# SMART_SOCKET.net
KiCad netlist of a schematic drawn in EAGLE
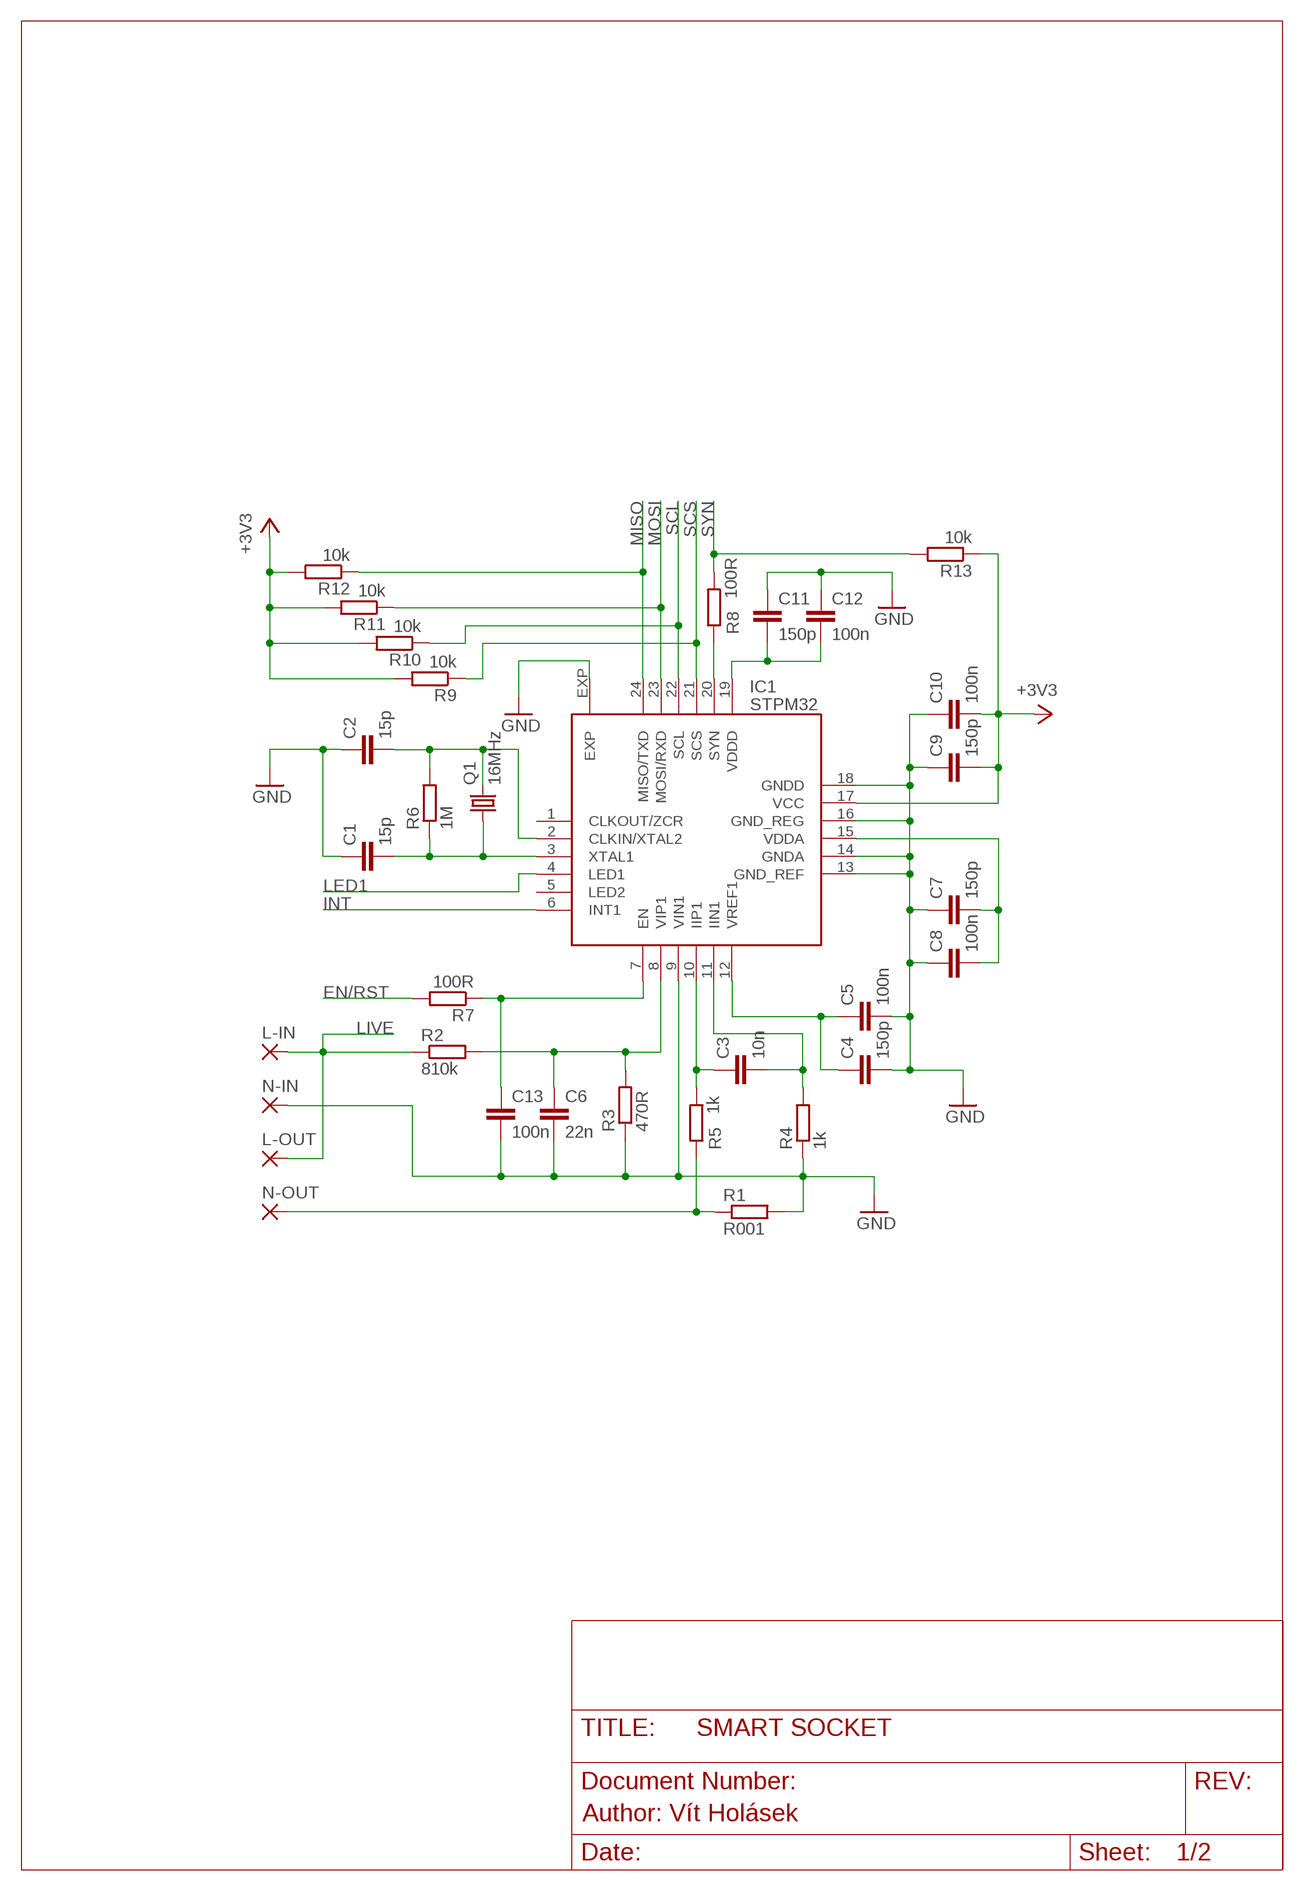
[diagram p0: schematic, sheet 1]
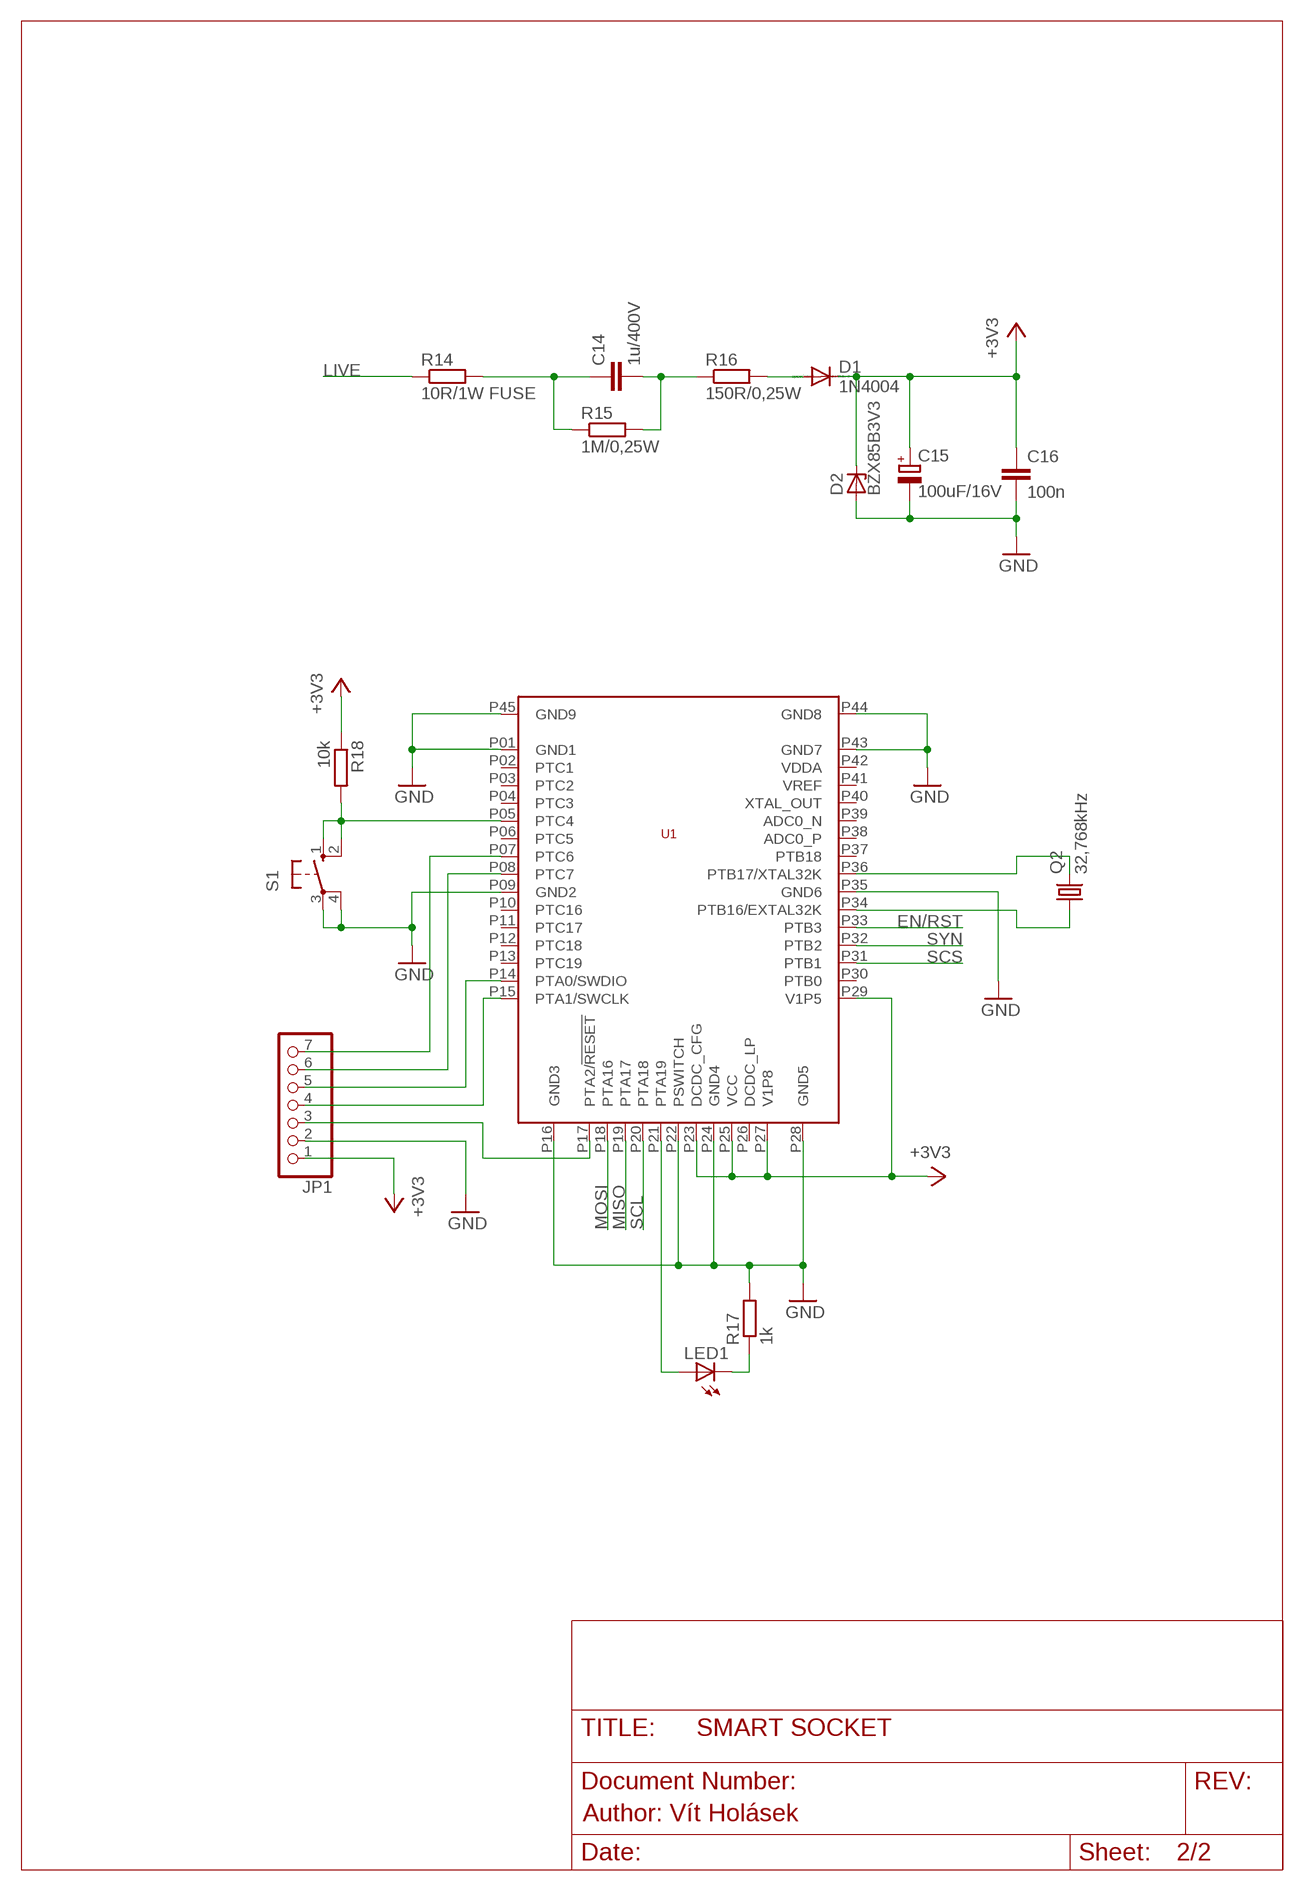
[diagram p1: schematic, sheet 2]

(export (version "E")
  (design (tool "Eeschema 10.0.6"))
  (components
    (comp (ref "C1")
      (value "15p")
      (footprint "eagle-import:C0402")
      (libsource (lib "eagle-import") (part "C-EUC0402"))
    )
    (comp (ref "C2")
      (value "15p")
      (footprint "eagle-import:C0402")
      (libsource (lib "eagle-import") (part "C-EUC0402"))
    )
    (comp (ref "C3")
      (value "10n")
      (footprint "eagle-import:C0402")
      (libsource (lib "eagle-import") (part "C-EUC0402"))
    )
    (comp (ref "C4")
      (value "150p")
      (footprint "eagle-import:C0402")
      (libsource (lib "eagle-import") (part "C-EUC0402"))
    )
    (comp (ref "C5")
      (value "100n")
      (footprint "eagle-import:C0402")
      (libsource (lib "eagle-import") (part "C-EUC0402"))
    )
    (comp (ref "C6")
      (value "22n")
      (footprint "eagle-import:C0603")
      (libsource (lib "eagle-import") (part "C-EUC0603"))
    )
    (comp (ref "C7")
      (value "150p")
      (footprint "eagle-import:C0402")
      (libsource (lib "eagle-import") (part "C-EUC0402"))
    )
    (comp (ref "C8")
      (value "100n")
      (footprint "eagle-import:C0402")
      (libsource (lib "eagle-import") (part "C-EUC0402"))
    )
    (comp (ref "C9")
      (value "150p")
      (footprint "eagle-import:C0402")
      (libsource (lib "eagle-import") (part "C-EUC0402"))
    )
    (comp (ref "C10")
      (value "100n")
      (footprint "eagle-import:C0402")
      (libsource (lib "eagle-import") (part "C-EUC0402"))
    )
    (comp (ref "C11")
      (value "150p")
      (footprint "eagle-import:C0402")
      (libsource (lib "eagle-import") (part "C-EUC0402"))
    )
    (comp (ref "C12")
      (value "100n")
      (footprint "eagle-import:C0402")
      (libsource (lib "eagle-import") (part "C-EUC0402"))
    )
    (comp (ref "C13")
      (value "100n")
      (footprint "eagle-import:C0603")
      (libsource (lib "eagle-import") (part "C-EUC0603"))
    )
    (comp (ref "IC1")
      (value "STPM32")
      (footprint "eagle-import:QFN24L")
      (libsource (lib "eagle-import") (part "STPM32"))
    )
    (comp (ref "L-IN")
      (value "2,54/1,1")
      (footprint "eagle-import:2,54_1,1")
      (libsource (lib "eagle-import") (part "2,54/1,1"))
    )
    (comp (ref "L-OUT")
      (value "2,54/1,1")
      (footprint "eagle-import:2,54_1,1")
      (libsource (lib "eagle-import") (part "2,54/1,1"))
    )
    (comp (ref "N-IN")
      (value "2,54/1,1")
      (footprint "eagle-import:2,54_1,1")
      (libsource (lib "eagle-import") (part "2,54/1,1"))
    )
    (comp (ref "N-OUT")
      (value "2,54/1,1")
      (footprint "eagle-import:2,54_1,1")
      (libsource (lib "eagle-import") (part "2,54/1,1"))
    )
    (comp (ref "Q1")
      (value "16MHz")
      (footprint "eagle-import:CTS406")
      (libsource (lib "eagle-import") (part "CRYSTALCTS406"))
    )
    (comp (ref "R1")
      (value "R001")
      (footprint "eagle-import:R2512")
      (libsource (lib "eagle-import") (part "R-EU_R2512"))
    )
    (comp (ref "R2")
      (value "810k")
      (footprint "eagle-import:R0603")
      (libsource (lib "eagle-import") (part "R-EU_R0603"))
    )
    (comp (ref "R3")
      (value "470R")
      (footprint "eagle-import:R0603")
      (libsource (lib "eagle-import") (part "R-EU_R0603"))
    )
    (comp (ref "R4")
      (value "1k")
      (footprint "eagle-import:R0402")
      (libsource (lib "eagle-import") (part "R-EU_R0402"))
    )
    (comp (ref "R5")
      (value "1k")
      (footprint "eagle-import:R0402")
      (libsource (lib "eagle-import") (part "R-EU_R0402"))
    )
    (comp (ref "R6")
      (value "1M")
      (footprint "eagle-import:R0402")
      (libsource (lib "eagle-import") (part "R-EU_R0402"))
    )
    (comp (ref "R7")
      (value "100R")
      (footprint "eagle-import:R0402")
      (libsource (lib "eagle-import") (part "R-EU_R0402"))
    )
    (comp (ref "R8")
      (value "100R")
      (footprint "eagle-import:R0402")
      (libsource (lib "eagle-import") (part "R-EU_R0402"))
    )
    (comp (ref "R9")
      (value "10k")
      (footprint "eagle-import:R0402")
      (libsource (lib "eagle-import") (part "R-EU_R0402"))
    )
    (comp (ref "R10")
      (value "10k")
      (footprint "eagle-import:R0402")
      (libsource (lib "eagle-import") (part "R-EU_R0402"))
    )
    (comp (ref "R11")
      (value "10k")
      (footprint "eagle-import:R0402")
      (libsource (lib "eagle-import") (part "R-EU_R0402"))
    )
    (comp (ref "R12")
      (value "10k")
      (footprint "eagle-import:R0402")
      (libsource (lib "eagle-import") (part "R-EU_R0402"))
    )
    (comp (ref "R13")
      (value "10k")
      (footprint "eagle-import:R0402")
      (libsource (lib "eagle-import") (part "R-EU_R0402"))
    )
    (comp (ref "C14")
      (value "1u/400V")
      (footprint "eagle-import:C0805")
      (libsource (lib "eagle-import") (part "C-EUC0805"))
    )
    (comp (ref "C15")
      (value "100uF/16V")
      (footprint "eagle-import:E5-8,5")
      (libsource (lib "eagle-import") (part "CPOL-EUE5-8.5"))
    )
    (comp (ref "C16")
      (value "100n")
      (footprint "eagle-import:C0603")
      (libsource (lib "eagle-import") (part "C-EUC0603"))
    )
    (comp (ref "D1")
      (value "1N4004")
      (footprint "eagle-import:DO41-10")
      (libsource (lib "eagle-import") (part "1N4004"))
    )
    (comp (ref "D2")
      (value "BZX85B3V3")
      (footprint "eagle-import:DO41Z10")
      (libsource (lib "eagle-import") (part "ZENER-DIODEDO41Z10"))
    )
    (comp (ref "JP1")
      (value "PINHD-1X7")
      (footprint "eagle-import:1X07")
      (libsource (lib "eagle-import") (part "PINHD-1X7"))
    )
    (comp (ref "LED1")
      (value "LED3MM")
      (footprint "eagle-import:LED3MM")
      (libsource (lib "eagle-import") (part "LED3MM"))
    )
    (comp (ref "Q2")
      (value "32,768kHz")
      (footprint "eagle-import:TC26V")
      (libsource (lib "eagle-import") (part "CRYSTALTC26V"))
    )
    (comp (ref "R14")
      (value "10R/1W FUSE")
      (footprint "eagle-import:0204_7")
      (libsource (lib "eagle-import") (part "R-EU_0204/7"))
    )
    (comp (ref "R15")
      (value "1M/0,25W")
      (footprint "eagle-import:R0805")
      (libsource (lib "eagle-import") (part "R-EU_R0805"))
    )
    (comp (ref "R16")
      (value "150R/0,25W")
      (footprint "eagle-import:R0805")
      (libsource (lib "eagle-import") (part "R-EU_R0805"))
    )
    (comp (ref "R17")
      (value "1k")
      (footprint "eagle-import:R0402")
      (libsource (lib "eagle-import") (part "R-EU_R0402"))
    )
    (comp (ref "R18")
      (value "10k")
      (footprint "eagle-import:R0402")
      (libsource (lib "eagle-import") (part "R-EU_R0402"))
    )
    (comp (ref "S1")
      (value "10-XX")
      (footprint "eagle-import:B3F-10XX")
      (fields (field (name "MPN") "B3F-1000"))
      (libsource (lib "eagle-import") (part "10-XX"))
    )
    (comp (ref "U1")
      (value "R41Z-T")
      (footprint "eagle-import:R41Z")
      (libsource (lib "eagle-import") (part "R41Z-T"))
    )
  )
  (nets
    (net (code "1") (name "+3V3") (class "Default")
      (node (ref "C10") (pin "2") (pinfunction "2_2") (pintype "passive"))
      (node (ref "C15") (pin "+") (pinfunction "+_+") (pintype "passive"))
      (node (ref "C16") (pin "1") (pinfunction "1_1") (pintype "passive"))
      (node (ref "C9") (pin "2") (pinfunction "2_2") (pintype "passive"))
      (node (ref "D1") (pin "C") (pinfunction "C_C") (pintype "passive"))
      (node (ref "D2") (pin "C") (pinfunction "C_C") (pintype "passive"))
      (node (ref "IC1") (pin "17") (pinfunction "VCC_17") (pintype "bidirectional"))
      (node (ref "JP1") (pin "1") (pinfunction "1_1") (pintype "passive"))
      (node (ref "R10") (pin "2") (pinfunction "2_2") (pintype "passive"))
      (node (ref "R11") (pin "2") (pinfunction "2_2") (pintype "passive"))
      (node (ref "R12") (pin "2") (pinfunction "2_2") (pintype "passive"))
      (node (ref "R13") (pin "1") (pinfunction "1_1") (pintype "passive"))
      (node (ref "R18") (pin "1") (pinfunction "1_1") (pintype "passive"))
      (node (ref "R9") (pin "2") (pinfunction "2_2") (pintype "passive"))
      (node (ref "U1") (pin "P23") (pinfunction "DCDC_CFG_P23") (pintype "bidirectional"))
      (node (ref "U1") (pin "P25") (pinfunction "VCC_P25") (pintype "bidirectional"))
      (node (ref "U1") (pin "P27") (pinfunction "V1P8_P27") (pintype "bidirectional"))
      (node (ref "U1") (pin "P29") (pinfunction "V1P5_P29") (pintype "bidirectional"))
    )
    (net (code "2") (name "EN{slash}RST") (class "Default")
      (node (ref "R7") (pin "2") (pinfunction "2_2") (pintype "passive"))
      (node (ref "U1") (pin "P33") (pinfunction "PTB3_P33") (pintype "bidirectional"))
    )
    (net (code "3") (name "GND") (class "Default")
      (node (ref "C1") (pin "1") (pinfunction "1_1") (pintype "passive"))
      (node (ref "C10") (pin "1") (pinfunction "1_1") (pintype "passive"))
      (node (ref "C11") (pin "1") (pinfunction "1_1") (pintype "passive"))
      (node (ref "C12") (pin "1") (pinfunction "1_1") (pintype "passive"))
      (node (ref "C13") (pin "2") (pinfunction "2_2") (pintype "passive"))
      (node (ref "C15") (pin "-") (pinfunction "-_-") (pintype "passive"))
      (node (ref "C16") (pin "2") (pinfunction "2_2") (pintype "passive"))
      (node (ref "C2") (pin "1") (pinfunction "1_1") (pintype "passive"))
      (node (ref "C4") (pin "2") (pinfunction "2_2") (pintype "passive"))
      (node (ref "C5") (pin "2") (pinfunction "2_2") (pintype "passive"))
      (node (ref "C6") (pin "2") (pinfunction "2_2") (pintype "passive"))
      (node (ref "C7") (pin "1") (pinfunction "1_1") (pintype "passive"))
      (node (ref "C8") (pin "1") (pinfunction "1_1") (pintype "passive"))
      (node (ref "C9") (pin "1") (pinfunction "1_1") (pintype "passive"))
      (node (ref "D2") (pin "A") (pinfunction "A_A") (pintype "passive"))
      (node (ref "IC1") (pin "13") (pinfunction "GND_REF_13") (pintype "bidirectional"))
      (node (ref "IC1") (pin "14") (pinfunction "GNDA_14") (pintype "bidirectional"))
      (node (ref "IC1") (pin "16") (pinfunction "GND_REG_16") (pintype "bidirectional"))
      (node (ref "IC1") (pin "18") (pinfunction "GNDD_18") (pintype "bidirectional"))
      (node (ref "IC1") (pin "9") (pinfunction "VIN1_9") (pintype "bidirectional"))
      (node (ref "IC1") (pin "EXP") (pinfunction "EXP_EXP") (pintype "bidirectional"))
      (node (ref "JP1") (pin "2") (pinfunction "2_2") (pintype "passive"))
      (node (ref "N-IN") (pin "1") (pinfunction "P_1") (pintype "passive"))
      (node (ref "R1") (pin "2") (pinfunction "2_2") (pintype "passive"))
      (node (ref "R17") (pin "2") (pinfunction "2_2") (pintype "passive"))
      (node (ref "R3") (pin "1") (pinfunction "1_1") (pintype "passive"))
      (node (ref "R4") (pin "1") (pinfunction "1_1") (pintype "passive"))
      (node (ref "S1") (pin "3") (pinfunction "P_3") (pintype "passive"))
      (node (ref "S1") (pin "4") (pinfunction "P1_4") (pintype "passive"))
      (node (ref "U1") (pin "P01") (pinfunction "GND1_P01") (pintype "bidirectional"))
      (node (ref "U1") (pin "P09") (pinfunction "GND2_P09") (pintype "bidirectional"))
      (node (ref "U1") (pin "P16") (pinfunction "GND3_P16") (pintype "bidirectional"))
      (node (ref "U1") (pin "P22") (pinfunction "PSWITCH_P22") (pintype "bidirectional"))
      (node (ref "U1") (pin "P24") (pinfunction "GND4_P24") (pintype "bidirectional"))
      (node (ref "U1") (pin "P28") (pinfunction "GND5_P28") (pintype "bidirectional"))
      (node (ref "U1") (pin "P35") (pinfunction "GND6_P35") (pintype "bidirectional"))
      (node (ref "U1") (pin "P43") (pinfunction "GND7_P43") (pintype "bidirectional"))
      (node (ref "U1") (pin "P44") (pinfunction "GND8_P44") (pintype "bidirectional"))
      (node (ref "U1") (pin "P45") (pinfunction "GND9_P45") (pintype "bidirectional"))
    )
    (net (code "4") (name "INT") (class "Default")
      (node (ref "IC1") (pin "6") (pinfunction "INT1_6") (pintype "bidirectional"))
    )
    (net (code "5") (name "LED1") (class "Default")
      (node (ref "IC1") (pin "4") (pinfunction "LED1_4") (pintype "bidirectional"))
    )
    (net (code "6") (name "LIVE") (class "Default")
      (node (ref "L-IN") (pin "1") (pinfunction "P_1") (pintype "passive"))
      (node (ref "L-OUT") (pin "1") (pinfunction "P_1") (pintype "passive"))
      (node (ref "R14") (pin "1") (pinfunction "1_1") (pintype "passive"))
      (node (ref "R2") (pin "1") (pinfunction "1_1") (pintype "passive"))
    )
    (net (code "7") (name "MISO") (class "Default")
      (node (ref "IC1") (pin "24") (pinfunction "MISO/TXD_24") (pintype "bidirectional"))
      (node (ref "R12") (pin "1") (pinfunction "1_1") (pintype "passive"))
      (node (ref "U1") (pin "P19") (pinfunction "PTA17_P19") (pintype "bidirectional"))
    )
    (net (code "8") (name "MOSI") (class "Default")
      (node (ref "IC1") (pin "23") (pinfunction "MOSI/RXD_23") (pintype "bidirectional"))
      (node (ref "R11") (pin "1") (pinfunction "1_1") (pintype "passive"))
      (node (ref "U1") (pin "P18") (pinfunction "PTA16_P18") (pintype "bidirectional"))
    )
    (net (code "9") (name "Net-(C14-Pad1)") (class "Default")
      (node (ref "C14") (pin "1") (pinfunction "1_1") (pintype "passive"))
      (node (ref "R14") (pin "2") (pinfunction "2_2") (pintype "passive"))
      (node (ref "R15") (pin "1") (pinfunction "1_1") (pintype "passive"))
    )
    (net (code "10") (name "Net-(C14-Pad2)") (class "Default")
      (node (ref "C14") (pin "2") (pinfunction "2_2") (pintype "passive"))
      (node (ref "R15") (pin "2") (pinfunction "2_2") (pintype "passive"))
      (node (ref "R16") (pin "1") (pinfunction "1_1") (pintype "passive"))
    )
    (net (code "11") (name "Net-(D1-PadA)") (class "Default")
      (node (ref "D1") (pin "A") (pinfunction "A_A") (pintype "passive"))
      (node (ref "R16") (pin "2") (pinfunction "2_2") (pintype "passive"))
    )
    (net (code "12") (name "Net-(IC1-CLKIN{slash}XTAL2)") (class "Default")
      (node (ref "C2") (pin "2") (pinfunction "2_2") (pintype "passive"))
      (node (ref "IC1") (pin "2") (pinfunction "CLKIN/XTAL2_2") (pintype "bidirectional"))
      (node (ref "Q1") (pin "3") (pinfunction "2_3") (pintype "passive"))
      (node (ref "R6") (pin "2") (pinfunction "2_2") (pintype "passive"))
    )
    (net (code "13") (name "Net-(IC1-EN)") (class "Default")
      (node (ref "C13") (pin "1") (pinfunction "1_1") (pintype "passive"))
      (node (ref "IC1") (pin "7") (pinfunction "EN_7") (pintype "bidirectional"))
      (node (ref "R7") (pin "1") (pinfunction "1_1") (pintype "passive"))
    )
    (net (code "14") (name "Net-(IC1-IIN1)") (class "Default")
      (node (ref "C3") (pin "2") (pinfunction "2_2") (pintype "passive"))
      (node (ref "IC1") (pin "11") (pinfunction "IIN1_11") (pintype "bidirectional"))
      (node (ref "R4") (pin "2") (pinfunction "2_2") (pintype "passive"))
    )
    (net (code "15") (name "Net-(IC1-IIP1)") (class "Default")
      (node (ref "C3") (pin "1") (pinfunction "1_1") (pintype "passive"))
      (node (ref "IC1") (pin "10") (pinfunction "IIP1_10") (pintype "bidirectional"))
      (node (ref "R5") (pin "2") (pinfunction "2_2") (pintype "passive"))
    )
    (net (code "16") (name "Net-(IC1-SYN)") (class "Default")
      (node (ref "IC1") (pin "20") (pinfunction "SYN_20") (pintype "bidirectional"))
      (node (ref "R8") (pin "1") (pinfunction "1_1") (pintype "passive"))
    )
    (net (code "17") (name "Net-(IC1-VDDA)") (class "Default")
      (node (ref "C7") (pin "2") (pinfunction "2_2") (pintype "passive"))
      (node (ref "C8") (pin "2") (pinfunction "2_2") (pintype "passive"))
      (node (ref "IC1") (pin "15") (pinfunction "VDDA_15") (pintype "bidirectional"))
    )
    (net (code "18") (name "Net-(IC1-VDDD)") (class "Default")
      (node (ref "C11") (pin "2") (pinfunction "2_2") (pintype "passive"))
      (node (ref "C12") (pin "2") (pinfunction "2_2") (pintype "passive"))
      (node (ref "IC1") (pin "19") (pinfunction "VDDD_19") (pintype "bidirectional"))
    )
    (net (code "19") (name "Net-(IC1-VIP1)") (class "Default")
      (node (ref "C6") (pin "1") (pinfunction "1_1") (pintype "passive"))
      (node (ref "IC1") (pin "8") (pinfunction "VIP1_8") (pintype "bidirectional"))
      (node (ref "R2") (pin "2") (pinfunction "2_2") (pintype "passive"))
      (node (ref "R3") (pin "2") (pinfunction "2_2") (pintype "passive"))
    )
    (net (code "20") (name "Net-(IC1-VREF1)") (class "Default")
      (node (ref "C4") (pin "1") (pinfunction "1_1") (pintype "passive"))
      (node (ref "C5") (pin "1") (pinfunction "1_1") (pintype "passive"))
      (node (ref "IC1") (pin "12") (pinfunction "VREF1_12") (pintype "bidirectional"))
    )
    (net (code "21") (name "Net-(IC1-XTAL1)") (class "Default")
      (node (ref "C1") (pin "2") (pinfunction "2_2") (pintype "passive"))
      (node (ref "IC1") (pin "3") (pinfunction "XTAL1_3") (pintype "bidirectional"))
      (node (ref "Q1") (pin "1") (pinfunction "1_1") (pintype "passive"))
      (node (ref "R6") (pin "1") (pinfunction "1_1") (pintype "passive"))
    )
    (net (code "22") (name "Net-(LED1-C)") (class "Default")
      (node (ref "LED1") (pin "K") (pinfunction "C_K") (pintype "passive"))
      (node (ref "R17") (pin "1") (pinfunction "1_1") (pintype "passive"))
    )
    (net (code "23") (name "Net-(N-OUT-P)") (class "Default")
      (node (ref "N-OUT") (pin "1") (pinfunction "P_1") (pintype "passive"))
      (node (ref "R1") (pin "1") (pinfunction "1_1") (pintype "passive"))
      (node (ref "R5") (pin "1") (pinfunction "1_1") (pintype "passive"))
    )
    (net (code "24") (name "Net-(S1-S)") (class "Default")
      (node (ref "R18") (pin "2") (pinfunction "2_2") (pintype "passive"))
      (node (ref "S1") (pin "1") (pinfunction "S_1") (pintype "passive"))
      (node (ref "S1") (pin "2") (pinfunction "S1_2") (pintype "passive"))
      (node (ref "U1") (pin "P05") (pinfunction "PTC4_P05") (pintype "bidirectional"))
    )
    (net (code "25") (name "Net-(U1-PTA0{slash}SWDIO)") (class "Default")
      (node (ref "JP1") (pin "5") (pinfunction "5_5") (pintype "passive"))
      (node (ref "U1") (pin "P14") (pinfunction "PTA0/SWDIO_P14") (pintype "bidirectional"))
    )
    (net (code "26") (name "Net-(U1-PTA1{slash}SWCLK)") (class "Default")
      (node (ref "JP1") (pin "4") (pinfunction "4_4") (pintype "passive"))
      (node (ref "U1") (pin "P15") (pinfunction "PTA1/SWCLK_P15") (pintype "bidirectional"))
    )
    (net (code "27") (name "Net-(U1-PTA2{slash}~{RESET})") (class "Default")
      (node (ref "JP1") (pin "3") (pinfunction "3_3") (pintype "passive"))
      (node (ref "U1") (pin "P17") (pinfunction "PTA2/~{RESET}_P17") (pintype "bidirectional"))
    )
    (net (code "28") (name "Net-(U1-PTA19)") (class "Default")
      (node (ref "LED1") (pin "A") (pinfunction "A_A") (pintype "passive"))
      (node (ref "U1") (pin "P21") (pinfunction "PTA19_P21") (pintype "bidirectional"))
    )
    (net (code "29") (name "Net-(U1-PTB16{slash}EXTAL32K)") (class "Default")
      (node (ref "Q2") (pin "1") (pinfunction "1_1") (pintype "passive"))
      (node (ref "U1") (pin "P34") (pinfunction "PTB16/EXTAL32K_P34") (pintype "bidirectional"))
    )
    (net (code "30") (name "Net-(U1-PTB17{slash}XTAL32K)") (class "Default")
      (node (ref "Q2") (pin "2") (pinfunction "2_2") (pintype "passive"))
      (node (ref "U1") (pin "P36") (pinfunction "PTB17/XTAL32K_P36") (pintype "bidirectional"))
    )
    (net (code "31") (name "Net-(U1-PTC6)") (class "Default")
      (node (ref "JP1") (pin "7") (pinfunction "7_7") (pintype "passive"))
      (node (ref "U1") (pin "P07") (pinfunction "PTC6_P07") (pintype "bidirectional"))
    )
    (net (code "32") (name "Net-(U1-PTC7)") (class "Default")
      (node (ref "JP1") (pin "6") (pinfunction "6_6") (pintype "passive"))
      (node (ref "U1") (pin "P08") (pinfunction "PTC7_P08") (pintype "bidirectional"))
    )
    (net (code "33") (name "SCL") (class "Default")
      (node (ref "IC1") (pin "22") (pinfunction "SCL_22") (pintype "bidirectional"))
      (node (ref "R10") (pin "1") (pinfunction "1_1") (pintype "passive"))
      (node (ref "U1") (pin "P20") (pinfunction "PTA18_P20") (pintype "bidirectional"))
    )
    (net (code "34") (name "SCS") (class "Default")
      (node (ref "IC1") (pin "21") (pinfunction "SCS_21") (pintype "bidirectional"))
      (node (ref "R9") (pin "1") (pinfunction "1_1") (pintype "passive"))
      (node (ref "U1") (pin "P31") (pinfunction "PTB1_P31") (pintype "bidirectional"))
    )
    (net (code "35") (name "SYN") (class "Default")
      (node (ref "R13") (pin "2") (pinfunction "2_2") (pintype "passive"))
      (node (ref "R8") (pin "2") (pinfunction "2_2") (pintype "passive"))
      (node (ref "U1") (pin "P32") (pinfunction "PTB2_P32") (pintype "bidirectional"))
    )
    (net (code "36") (name "unconnected-(IC1-CLKOUT{slash}ZCR-Pad1)") (class "Default")
      (node (ref "IC1") (pin "1") (pinfunction "CLKOUT/ZCR_1") (pintype "bidirectional"))
    )
    (net (code "37") (name "unconnected-(IC1-LED2-Pad5)") (class "Default")
      (node (ref "IC1") (pin "5") (pinfunction "LED2_5") (pintype "bidirectional"))
    )
    (net (code "38") (name "unconnected-(U1-ADC0_N-PadP39)") (class "Default")
      (node (ref "U1") (pin "P39") (pinfunction "ADC0_N_P39") (pintype "bidirectional"))
    )
    (net (code "39") (name "unconnected-(U1-ADC0_P-PadP38)") (class "Default")
      (node (ref "U1") (pin "P38") (pinfunction "ADC0_P_P38") (pintype "bidirectional"))
    )
    (net (code "40") (name "unconnected-(U1-DCDC_LP-PadP26)") (class "Default")
      (node (ref "U1") (pin "P26") (pinfunction "DCDC_LP_P26") (pintype "bidirectional"))
    )
    (net (code "41") (name "unconnected-(U1-PTB0-PadP30)") (class "Default")
      (node (ref "U1") (pin "P30") (pinfunction "PTB0_P30") (pintype "bidirectional"))
    )
    (net (code "42") (name "unconnected-(U1-PTB18-PadP37)") (class "Default")
      (node (ref "U1") (pin "P37") (pinfunction "PTB18_P37") (pintype "bidirectional"))
    )
    (net (code "43") (name "unconnected-(U1-PTC1-PadP02)") (class "Default")
      (node (ref "U1") (pin "P02") (pinfunction "PTC1_P02") (pintype "bidirectional"))
    )
    (net (code "44") (name "unconnected-(U1-PTC2-PadP03)") (class "Default")
      (node (ref "U1") (pin "P03") (pinfunction "PTC2_P03") (pintype "bidirectional"))
    )
    (net (code "45") (name "unconnected-(U1-PTC3-PadP04)") (class "Default")
      (node (ref "U1") (pin "P04") (pinfunction "PTC3_P04") (pintype "bidirectional"))
    )
    (net (code "46") (name "unconnected-(U1-PTC5-PadP06)") (class "Default")
      (node (ref "U1") (pin "P06") (pinfunction "PTC5_P06") (pintype "bidirectional"))
    )
    (net (code "47") (name "unconnected-(U1-PTC16-PadP10)") (class "Default")
      (node (ref "U1") (pin "P10") (pinfunction "PTC16_P10") (pintype "bidirectional"))
    )
    (net (code "48") (name "unconnected-(U1-PTC17-PadP11)") (class "Default")
      (node (ref "U1") (pin "P11") (pinfunction "PTC17_P11") (pintype "bidirectional"))
    )
    (net (code "49") (name "unconnected-(U1-PTC18-PadP12)") (class "Default")
      (node (ref "U1") (pin "P12") (pinfunction "PTC18_P12") (pintype "bidirectional"))
    )
    (net (code "50") (name "unconnected-(U1-PTC19-PadP13)") (class "Default")
      (node (ref "U1") (pin "P13") (pinfunction "PTC19_P13") (pintype "bidirectional"))
    )
    (net (code "51") (name "unconnected-(U1-VDDA-PadP42)") (class "Default")
      (node (ref "U1") (pin "P42") (pinfunction "VDDA_P42") (pintype "bidirectional"))
    )
    (net (code "52") (name "unconnected-(U1-VREF-PadP41)") (class "Default")
      (node (ref "U1") (pin "P41") (pinfunction "VREF_P41") (pintype "bidirectional"))
    )
    (net (code "53") (name "unconnected-(U1-XTAL_OUT-PadP40)") (class "Default")
      (node (ref "U1") (pin "P40") (pinfunction "XTAL_OUT_P40") (pintype "bidirectional"))
    )
  )
)
